# Photography_Light.net
KiCad netlist of a schematic drawn in Altium Designer
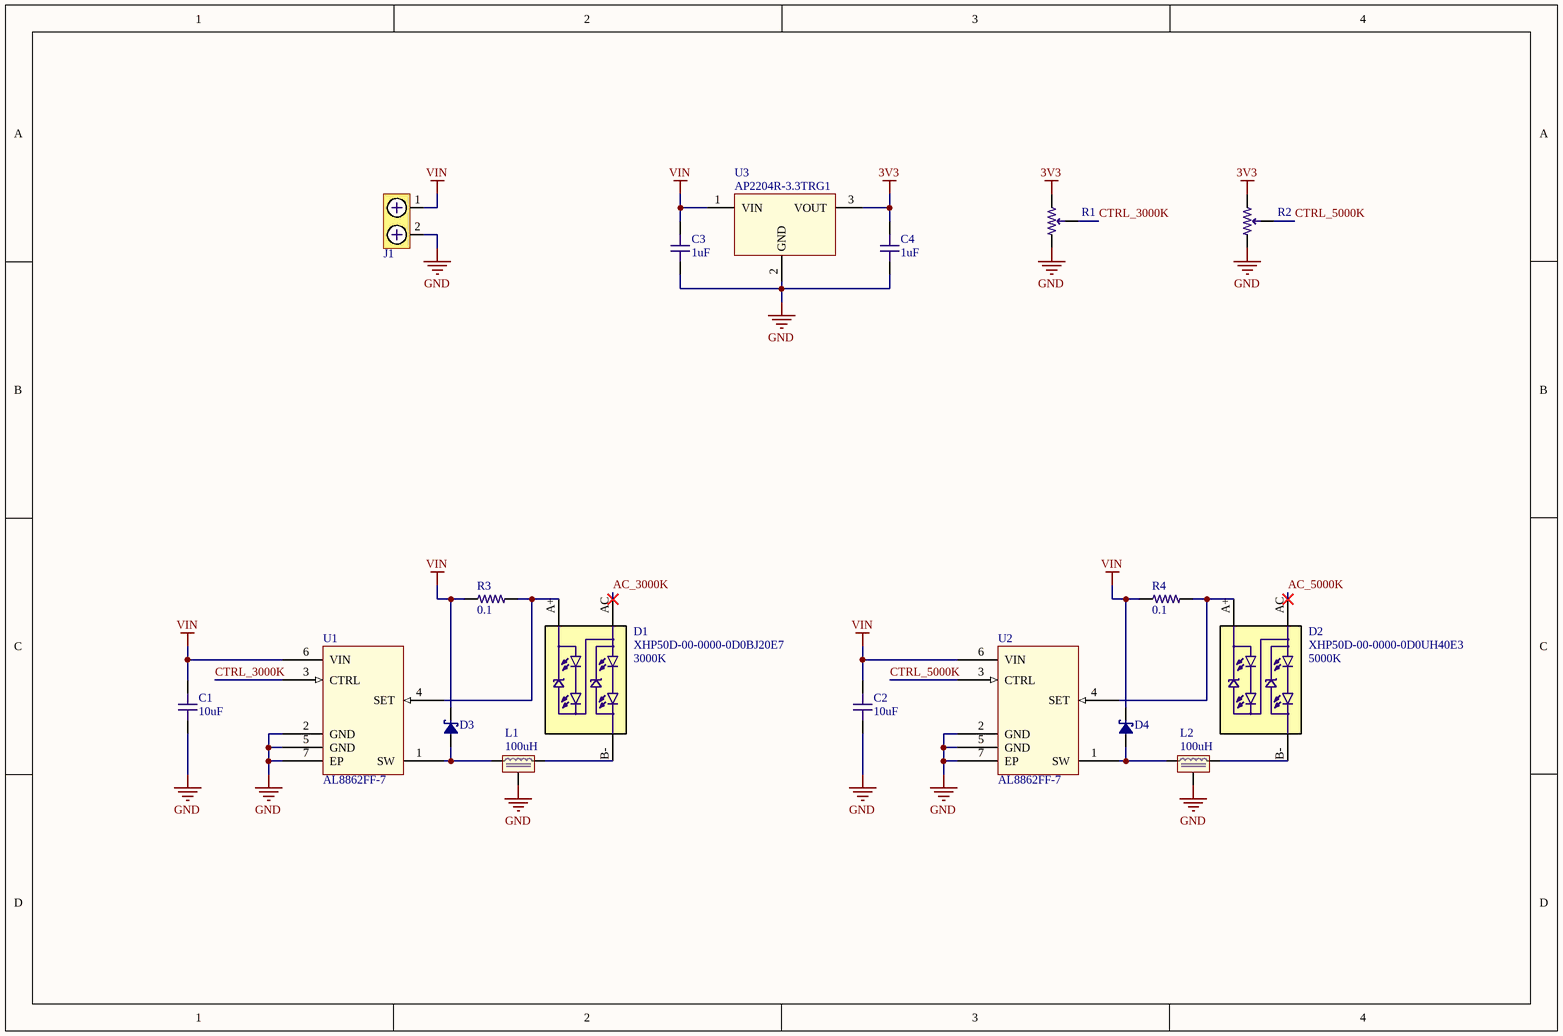
[diagram p0: Photography_Light.SchDoc]

(export (version "E")
  (design (tool "Eeschema 10.0.6"))
  (components
    (comp (ref "C1")
      (value "10uF")
      (footprint "C1206-IPC")
      (description "CAP CER 10UF 35V X7R 1206")
      (fields (field (name "Comment") "C1206 10uF 35V X7R"))
      (libsource (lib "Capacitors") (part "C1206 10uF 25V X7R"))
    )
    (comp (ref "C2")
      (value "10uF")
      (footprint "C1206-IPC")
      (description "CAP CER 10UF 35V X7R 1206")
      (fields (field (name "Comment") "C1206 10uF 35V X7R"))
      (libsource (lib "Capacitors") (part "C1206 10uF 25V X7R"))
    )
    (comp (ref "C3")
      (value "1uF")
      (footprint "C0603-IPC")
      (description "CAP CER 1UF 50V X7R 0603")
      (fields (field (name "Comment") "C0603 1uF 50V X7R"))
      (libsource (lib "Capacitors") (part "C0603 1uF 50V X7R"))
    )
    (comp (ref "C4")
      (value "1uF")
      (footprint "C0603-IPC")
      (description "CAP CER 1UF 50V X7R 0603")
      (fields (field (name "Comment") "C0603 1uF 50V X7R"))
      (libsource (lib "Capacitors") (part "C0603 1uF 50V X7R"))
    )
    (comp (ref "D1")
      (value "XHP50D-00-0000-0D0BJ20E7")
      (footprint "LED_XHP50B - 12V Configuration Only")
      (description "3000K LED Lighting series White, Warm 3000K 11.2V 700mA 120° 2020 (5050 Metric)")
      (fields (field (name "MF") "Cree Inc."))
      (libsource (lib "Diodes") (part "XHP50D-00-0000-0D0BJ20E7"))
    )
    (comp (ref "D2")
      (value "XHP50D-00-0000-0D0UH40E3")
      (footprint "LED_XHP50B - 12V Configuration Only")
      (description "5000K LED Lighting series White, Cool 5000K 11.2V 700mA 120° 2020 (5050 Metric)")
      (fields (field (name "MF") "Cree Inc."))
      (libsource (lib "Diodes") (part "XHP50D-00-0000-0D0UH40E3"))
    )
    (comp (ref "D3")
      (value "SK56AFL-TP")
      (footprint "DO221AC (SMA-FL)")
      (description "Diode Schottky 60 V 5A Surface Mount DO-221AC (SMA-FL)")
      (libsource (lib "Diodes") (part "SK56AFL-TP"))
    )
    (comp (ref "D4")
      (value "SK56AFL-TP")
      (footprint "DO221AC (SMA-FL)")
      (description "Diode Schottky 60 V 5A Surface Mount DO-221AC (SMA-FL)")
      (libsource (lib "Diodes") (part "SK56AFL-TP"))
    )
    (comp (ref "J1")
      (value "Phoenix Contact 1935161")
      (footprint "Phoenix_1935161")
      (description "Terminal Block, 2 Position, 5mm pitch, 18A, 300V, 12-26 AWG")
      (fields
        (field (name "MANUFACTURER") "Phoenix Contact")
        (field (name "MANUFACTURER PART NUMBER") "1935161")
      )
      (libsource (lib "Connectors") (part "Term Block 2pos"))
    )
    (comp (ref "L1")
      (value "100uH")
      (footprint "IHLE-5050FH-51")
      (description "100 µH Shielded Wirewound Inductor 3.1 A 205mOhm Max Nonstandard")
      (fields (field (name "Comment") "IHLE5050FHER101M51"))
      (libsource (lib "Inductors") (part "IHLE-5050FH-51"))
    )
    (comp (ref "L2")
      (value "100uH")
      (footprint "IHLE-5050FH-51")
      (description "100 µH Shielded Wirewound Inductor 3.1 A 205mOhm Max Nonstandard")
      (fields (field (name "Comment") "IHLE5050FHER101M51"))
      (libsource (lib "Inductors") (part "IHLE-5050FH-51"))
    )
    (comp (ref "R1")
      (value "CTRL_3000K")
      (footprint "TRIM_3352T-1-103LF")
      (description "10 kOhms 0.5W, 1/2W Through Hole Thumbwheel Potentiometer Top Adjustment")
      (libsource (lib "Resistors") (part "RPot 10k Thumbwheel"))
    )
    (comp (ref "R2")
      (value "CTRL_5000K")
      (footprint "TRIM_3352T-1-103LF")
      (description "10 kOhms 0.5W, 1/2W Through Hole Thumbwheel Potentiometer Top Adjustment")
      (libsource (lib "Resistors") (part "RPot 10k Thumbwheel"))
    )
    (comp (ref "R3")
      (value "0.1")
      (footprint "R2512-IPC")
      (description "Chip Resistor, 2512, 0.1 ohms, 3W")
      (fields (field (name "Comment") "R2512 0.1R 1%"))
      (libsource (lib "Resistors") (part "R2512 0.1R 1%"))
    )
    (comp (ref "R4")
      (value "0.1")
      (footprint "R2512-IPC")
      (description "Chip Resistor, 2512, 0.1 ohms, 3W")
      (fields (field (name "Comment") "R2512 0.1R 1%"))
      (libsource (lib "Resistors") (part "R2512 0.1R 1%"))
    )
    (comp (ref "U1")
      (value "AL8862FF-7")
      (footprint "U-DFN3030-6")
      (description "LED Driver IC 1 Output DC DC Regulator Step-Down (Buck) Analog, PWM Dimming 1A 6-DFN (3x3)")
      (libsource (lib "Integrated Circuits") (part "AL8862FF-7"))
    )
    (comp (ref "U2")
      (value "AL8862FF-7")
      (footprint "U-DFN3030-6")
      (description "LED Driver IC 1 Output DC DC Regulator Step-Down (Buck) Analog, PWM Dimming 1A 6-DFN (3x3)")
      (libsource (lib "Integrated Circuits") (part "AL8862FF-7"))
    )
    (comp (ref "U3")
      (value "AP2204R-3.3TRG1")
      (footprint "SOT-89")
      (description "Fixed 24V 3.3V 150mA SOT-89(SOT-89-3) Low Dropout Regulators(LDO)")
      (libsource (lib "Integrated Circuits") (part "AP2204R-3.3TRG1"))
    )
  )
  (nets
    (net (code "1") (name "/AC_3000K") (class "Default")
      (node (ref "D1") (pin "AC") (pinfunction "AC_AC") (pintype "passive+no_connect"))
    )
    (net (code "2") (name "/AC_5000K") (class "Default")
      (node (ref "D2") (pin "AC") (pinfunction "AC_AC") (pintype "passive+no_connect"))
    )
    (net (code "3") (name "/CTRL_3000K") (class "Default")
      (node (ref "R1") (pin "2") (pinfunction "W_2") (pintype "passive"))
      (node (ref "U1") (pin "3") (pinfunction "CTRL_3") (pintype "input"))
    )
    (net (code "4") (name "/CTRL_5000K") (class "Default")
      (node (ref "R2") (pin "2") (pinfunction "W_2") (pintype "passive"))
      (node (ref "U2") (pin "3") (pinfunction "CTRL_3") (pintype "input"))
    )
    (net (code "5") (name "3V3") (class "Default")
      (node (ref "C4") (pin "2") (pintype "passive"))
      (node (ref "R1") (pin "3") (pinfunction "CW_3") (pintype "passive"))
      (node (ref "R2") (pin "3") (pinfunction "CW_3") (pintype "passive"))
      (node (ref "U3") (pin "3") (pinfunction "VOUT_3") (pintype "passive"))
    )
    (net (code "6") (name "GND") (class "Default")
      (node (ref "C1") (pin "1") (pintype "passive"))
      (node (ref "C2") (pin "1") (pintype "passive"))
      (node (ref "C3") (pin "1") (pintype "passive"))
      (node (ref "C4") (pin "1") (pintype "passive"))
      (node (ref "J1") (pin "2") (pintype "passive"))
      (node (ref "L1") (pin "SHIELD") (pintype "passive"))
      (node (ref "L2") (pin "SHIELD") (pintype "passive"))
      (node (ref "R1") (pin "1") (pinfunction "CCW_1") (pintype "passive"))
      (node (ref "R2") (pin "1") (pinfunction "CCW_1") (pintype "passive"))
      (node (ref "U1") (pin "2") (pinfunction "GND_2") (pintype "power_in"))
      (node (ref "U1") (pin "5") (pinfunction "GND_5") (pintype "power_in"))
      (node (ref "U1") (pin "7") (pinfunction "EP_7") (pintype "power_in"))
      (node (ref "U2") (pin "2") (pinfunction "GND_2") (pintype "power_in"))
      (node (ref "U2") (pin "5") (pinfunction "GND_5") (pintype "power_in"))
      (node (ref "U2") (pin "7") (pinfunction "EP_7") (pintype "power_in"))
      (node (ref "U3") (pin "2") (pinfunction "GND_2") (pintype "passive"))
    )
    (net (code "7") (name "Net-(D1-PadB-)") (class "Default")
      (node (ref "D1") (pin "B-") (pinfunction "B-_B-") (pintype "passive"))
      (node (ref "L1") (pin "2") (pintype "passive"))
    )
    (net (code "8") (name "Net-(D2-PadB-)") (class "Default")
      (node (ref "D2") (pin "B-") (pinfunction "B-_B-") (pintype "passive"))
      (node (ref "L2") (pin "2") (pintype "passive"))
    )
    (net (code "9") (name "Net-(U1-SET)") (class "Default")
      (node (ref "D1") (pin "A+") (pinfunction "A+_A+") (pintype "passive"))
      (node (ref "R3") (pin "1") (pintype "passive"))
      (node (ref "U1") (pin "4") (pinfunction "SET_4") (pintype "input"))
    )
    (net (code "10") (name "Net-(U1-SW)") (class "Default")
      (node (ref "D3") (pin "A") (pinfunction "A_A") (pintype "passive"))
      (node (ref "L1") (pin "1") (pintype "passive"))
      (node (ref "U1") (pin "1") (pinfunction "SW_1") (pintype "passive"))
    )
    (net (code "11") (name "Net-(U2-SET)") (class "Default")
      (node (ref "D2") (pin "A+") (pinfunction "A+_A+") (pintype "passive"))
      (node (ref "R4") (pin "1") (pintype "passive"))
      (node (ref "U2") (pin "4") (pinfunction "SET_4") (pintype "input"))
    )
    (net (code "12") (name "Net-(U2-SW)") (class "Default")
      (node (ref "D4") (pin "A") (pinfunction "A_A") (pintype "passive"))
      (node (ref "L2") (pin "1") (pintype "passive"))
      (node (ref "U2") (pin "1") (pinfunction "SW_1") (pintype "passive"))
    )
    (net (code "13") (name "VIN") (class "Default")
      (node (ref "C1") (pin "2") (pintype "passive"))
      (node (ref "C2") (pin "2") (pintype "passive"))
      (node (ref "C3") (pin "2") (pintype "passive"))
      (node (ref "D3") (pin "K") (pinfunction "K_K") (pintype "passive"))
      (node (ref "D4") (pin "K") (pinfunction "K_K") (pintype "passive"))
      (node (ref "J1") (pin "1") (pintype "passive"))
      (node (ref "R3") (pin "2") (pintype "passive"))
      (node (ref "R4") (pin "2") (pintype "passive"))
      (node (ref "U1") (pin "6") (pinfunction "VIN_6") (pintype "power_in"))
      (node (ref "U2") (pin "6") (pinfunction "VIN_6") (pintype "power_in"))
      (node (ref "U3") (pin "1") (pinfunction "VIN_1") (pintype "passive"))
    )
  )
)
